# main.net
KiCad netlist of a schematic drawn in EAGLE
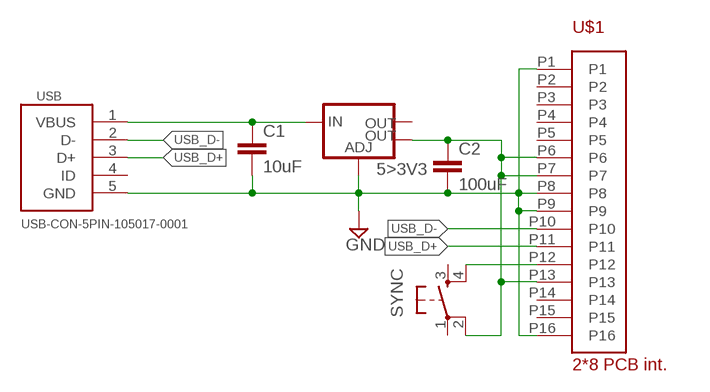
[diagram p0: schematic, sheet 1]

(export (version "E")
  (design (tool "Eeschema 10.0.6"))
  (components
    (comp (ref "5>3V3")
      (value "V_REG_LM1117SOT223")
      (footprint "eagle-import:SOT223")
      (libsource (lib "eagle-import") (part "V_REG_LM1117SOT223"))
    )
    (comp (ref "C1")
      (value "10uF")
      (footprint "eagle-import:C0805")
      (libsource (lib "eagle-import") (part "C-EUC0805"))
    )
    (comp (ref "C2")
      (value "100uF")
      (footprint "eagle-import:C0805")
      (libsource (lib "eagle-import") (part "C-EUC0805"))
    )
    (comp (ref "SYNC")
      (value "TAC_SWITCHPTH")
      (footprint "eagle-import:TACTILE-PTH")
      (libsource (lib "eagle-import") (part "TAC_SWITCHPTH"))
    )
    (comp (ref "U$1")
      (value "MOLEX_0541020164MOLEX")
      (footprint "eagle-import:MOLEX_0541020164")
      (libsource (lib "eagle-import") (part "MOLEX_0541020164MOLEX"))
    )
    (comp (ref "USB")
      (value "USB-CON-5PIN-105017-0001")
      (footprint "eagle-import:USB-MICRO-MOLEX-105017-0001")
      (libsource (lib "eagle-import") (part "USB-CON-5PIN-105017-0001"))
    )
  )
  (nets
    (net (code "1") (name "GND") (class "Default")
      (node (ref "5>3V3") (pin "1") (pinfunction "ADJ_1") (pintype "input"))
      (node (ref "C1") (pin "2") (pinfunction "2_2") (pintype "passive"))
      (node (ref "C2") (pin "2") (pinfunction "2_2") (pintype "passive"))
      (node (ref "U$1") (pin "P1") (pinfunction "P1_P1") (pintype "bidirectional"))
      (node (ref "U$1") (pin "P16") (pinfunction "P16_P16") (pintype "bidirectional"))
      (node (ref "U$1") (pin "P8") (pinfunction "P8_P8") (pintype "bidirectional"))
      (node (ref "U$1") (pin "P9") (pinfunction "P9_P9") (pintype "bidirectional"))
      (node (ref "USB") (pin "5") (pinfunction "GND_5") (pintype "power_in"))
    )
    (net (code "2") (name "Net-(5>3V3-IN)") (class "Default")
      (node (ref "5>3V3") (pin "3") (pinfunction "IN_3") (pintype "input"))
      (node (ref "C1") (pin "1") (pinfunction "1_1") (pintype "passive"))
      (node (ref "USB") (pin "1") (pinfunction "VBUS_1") (pintype "power_in"))
    )
    (net (code "3") (name "Net-(5>3V3-OUT-Pad4)") (class "Default")
      (node (ref "5>3V3") (pin "4") (pinfunction "OUT_4") (pintype "output"))
      (node (ref "C2") (pin "1") (pinfunction "1_1") (pintype "passive"))
      (node (ref "SYNC") (pin "2") (pinfunction "2_2") (pintype "passive"))
      (node (ref "U$1") (pin "P13") (pinfunction "P13_P13") (pintype "bidirectional"))
      (node (ref "U$1") (pin "P6") (pinfunction "P6_P6") (pintype "bidirectional"))
      (node (ref "U$1") (pin "P7") (pinfunction "P7_P7") (pintype "bidirectional"))
    )
    (net (code "4") (name "Net-(SYNC-Pad4)") (class "Default")
      (node (ref "SYNC") (pin "4") (pinfunction "4_4") (pintype "passive"))
      (node (ref "U$1") (pin "P12") (pinfunction "P12_P12") (pintype "bidirectional"))
    )
    (net (code "5") (name "USB_D+") (class "Default")
      (node (ref "U$1") (pin "P11") (pinfunction "P11_P11") (pintype "bidirectional"))
      (node (ref "USB") (pin "3") (pinfunction "D+_3") (pintype "bidirectional"))
    )
    (net (code "6") (name "USB_D-") (class "Default")
      (node (ref "U$1") (pin "P10") (pinfunction "P10_P10") (pintype "bidirectional"))
      (node (ref "USB") (pin "2") (pinfunction "D-_2") (pintype "bidirectional"))
    )
    (net (code "7") (name "unconnected-(5>3V3-OUT-Pad2)") (class "Default")
      (node (ref "5>3V3") (pin "2") (pinfunction "OUT_2") (pintype "output"))
    )
    (net (code "8") (name "unconnected-(SYNC-Pad1)") (class "Default")
      (node (ref "SYNC") (pin "1") (pinfunction "1_1") (pintype "passive"))
    )
    (net (code "9") (name "unconnected-(SYNC-Pad3)") (class "Default")
      (node (ref "SYNC") (pin "3") (pinfunction "3_3") (pintype "passive"))
    )
    (net (code "10") (name "unconnected-(U$1-PadP2)") (class "Default")
      (node (ref "U$1") (pin "P2") (pinfunction "P2_P2") (pintype "bidirectional"))
    )
    (net (code "11") (name "unconnected-(U$1-PadP3)") (class "Default")
      (node (ref "U$1") (pin "P3") (pinfunction "P3_P3") (pintype "bidirectional"))
    )
    (net (code "12") (name "unconnected-(U$1-PadP4)") (class "Default")
      (node (ref "U$1") (pin "P4") (pinfunction "P4_P4") (pintype "bidirectional"))
    )
    (net (code "13") (name "unconnected-(U$1-PadP5)") (class "Default")
      (node (ref "U$1") (pin "P5") (pinfunction "P5_P5") (pintype "bidirectional"))
    )
    (net (code "14") (name "unconnected-(U$1-PadP14)") (class "Default")
      (node (ref "U$1") (pin "P14") (pinfunction "P14_P14") (pintype "bidirectional"))
    )
    (net (code "15") (name "unconnected-(U$1-PadP15)") (class "Default")
      (node (ref "U$1") (pin "P15") (pinfunction "P15_P15") (pintype "bidirectional"))
    )
    (net (code "16") (name "unconnected-(USB-ID-Pad4)") (class "Default")
      (node (ref "USB") (pin "4") (pinfunction "ID_4") (pintype "bidirectional"))
    )
  )
)
